# INA226-Current-Sensors.net
KiCad netlist of a schematic drawn in Altium Designer
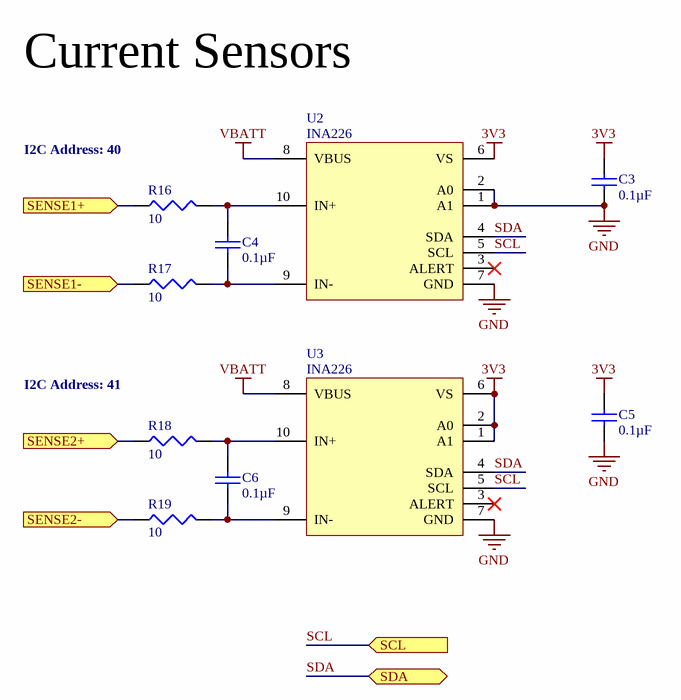
[diagram p0: INA226-Current-Sensors.SchDoc]

(export (version "E")
  (design (tool "Eeschema 10.0.6"))
  (components
    (comp (ref "C3")
      (value "0.1µF")
      (footprint "TDK-CGA2B")
      (description "CAP CER 0.1UF 50V X7R 0402")
      (fields
        (field (name "PART NUMBER") "PC-TDK-02262")
        (field (name "MANUFACTURER PART NUMBER") "CGA2B3X7R1H104M050BB")
        (field (name "PUBLISHER") "AlbertaSat")
      )
      (libsource (lib "Database") (part "Cap"))
    )
    (comp (ref "C4")
      (value "0.1µF")
      (footprint "TDK-CGA5L")
      (description "CAP CER 0.1UF 50V NP0 1206")
      (fields
        (field (name "PART NUMBER") "PC-TDK-02295")
        (field (name "MANUFACTURER PART NUMBER") "CGA5L2NP01H104J160AA")
        (field (name "PUBLISHER") "AlbertaSat")
      )
      (libsource (lib "Database") (part "Cap"))
    )
    (comp (ref "C5")
      (value "0.1µF")
      (footprint "TDK-CGA2B")
      (description "CAP CER 0.1UF 50V X7R 0402")
      (fields
        (field (name "PART NUMBER") "PC-TDK-02262")
        (field (name "MANUFACTURER PART NUMBER") "CGA2B3X7R1H104M050BB")
        (field (name "PUBLISHER") "AlbertaSat")
      )
      (libsource (lib "Database") (part "Cap"))
    )
    (comp (ref "C6")
      (value "0.1µF")
      (footprint "TDK-CGA5L")
      (description "CAP CER 0.1UF 50V NP0 1206")
      (fields
        (field (name "PART NUMBER") "PC-TDK-02295")
        (field (name "MANUFACTURER PART NUMBER") "CGA5L2NP01H104J160AA")
        (field (name "PUBLISHER") "AlbertaSat")
      )
      (libsource (lib "Database") (part "Cap"))
    )
    (comp (ref "R16")
      (value "10")
      (footprint "PANA-ERA2A")
      (description "RES SMD 10 OHM 0.5% 1/16W 0402")
      (fields
        (field (name "PART NUMBER") "13235")
        (field (name "MANUFACTURER PART NUMBER") "ERA-2AKD100X")
        (field (name "PUBLISHER") "Altium Limited")
      )
      (libsource (lib "Database") (part "Res3"))
    )
    (comp (ref "R17")
      (value "10")
      (footprint "PANA-ERA2A")
      (description "RES SMD 10 OHM 0.5% 1/16W 0402")
      (fields
        (field (name "PART NUMBER") "13235")
        (field (name "MANUFACTURER PART NUMBER") "ERA-2AKD100X")
        (field (name "PUBLISHER") "Altium Limited")
      )
      (libsource (lib "Database") (part "Res3"))
    )
    (comp (ref "R18")
      (value "10")
      (footprint "PANA-ERA2A")
      (description "RES SMD 10 OHM 0.5% 1/16W 0402")
      (fields
        (field (name "PART NUMBER") "13235")
        (field (name "MANUFACTURER PART NUMBER") "ERA-2AKD100X")
        (field (name "PUBLISHER") "Altium Limited")
      )
      (libsource (lib "Database") (part "Res3"))
    )
    (comp (ref "R19")
      (value "10")
      (footprint "PANA-ERA2A")
      (description "RES SMD 10 OHM 0.5% 1/16W 0402")
      (fields
        (field (name "PART NUMBER") "13235")
        (field (name "MANUFACTURER PART NUMBER") "ERA-2AKD100X")
        (field (name "PUBLISHER") "Altium Limited")
      )
      (libsource (lib "Database") (part "Res3"))
    )
    (comp (ref "U2")
      (value "INA226")
      (footprint "TI-DGS")
      (description "IC MONITOR PWR/CURR BIDIR 10MSOP")
      (fields (field (name "PART NUMBER") "19") (field (name "MANUFACTURER PART NUMBER") "INA226AQDGSRQ1"))
      (libsource (lib "Database") (part "INA226AQ"))
    )
    (comp (ref "U3")
      (value "INA226")
      (footprint "TI-DGS")
      (description "IC MONITOR PWR/CURR BIDIR 10MSOP")
      (fields (field (name "PART NUMBER") "19") (field (name "MANUFACTURER PART NUMBER") "INA226AQDGSRQ1"))
      (libsource (lib "Database") (part "INA226AQ"))
    )
  )
  (nets
    (net (code "2") (name "/SCL") (class "Default")
      (node (ref "U2") (pin "5") (pinfunction "SCL_5") (pintype "passive"))
      (node (ref "U3") (pin "5") (pinfunction "SCL_5") (pintype "passive"))
    )
    (net (code "3") (name "/SDA") (class "Default")
      (node (ref "U2") (pin "4") (pinfunction "SDA_4") (pintype "passive"))
      (node (ref "U3") (pin "4") (pinfunction "SDA_4") (pintype "passive"))
    )
    (net (code "4") (name "/SENSE1+") (class "Default")
      (node (ref "R16") (pin "1") (pinfunction "1_1") (pintype "passive"))
    )
    (net (code "5") (name "/SENSE1-") (class "Default")
      (node (ref "R17") (pin "1") (pinfunction "1_1") (pintype "passive"))
    )
    (net (code "6") (name "/SENSE2+") (class "Default")
      (node (ref "R18") (pin "1") (pinfunction "1_1") (pintype "passive"))
    )
    (net (code "7") (name "/SENSE2-") (class "Default")
      (node (ref "R19") (pin "1") (pinfunction "1_1") (pintype "passive"))
    )
    (net (code "8") (name "3V3") (class "Default")
      (node (ref "C3") (pin "2") (pinfunction "2_2") (pintype "passive"))
      (node (ref "C5") (pin "2") (pinfunction "2_2") (pintype "passive"))
      (node (ref "U2") (pin "6") (pinfunction "VS_6") (pintype "passive"))
      (node (ref "U3") (pin "1") (pinfunction "A1_1") (pintype "passive"))
      (node (ref "U3") (pin "2") (pinfunction "A0_2") (pintype "passive"))
      (node (ref "U3") (pin "6") (pinfunction "VS_6") (pintype "passive"))
    )
    (net (code "9") (name "GND") (class "Default")
      (node (ref "C3") (pin "1") (pinfunction "1_1") (pintype "passive"))
      (node (ref "C5") (pin "1") (pinfunction "1_1") (pintype "passive"))
      (node (ref "U2") (pin "1") (pinfunction "A1_1") (pintype "passive"))
      (node (ref "U2") (pin "2") (pinfunction "A0_2") (pintype "passive"))
      (node (ref "U2") (pin "7") (pinfunction "GND_7") (pintype "passive"))
      (node (ref "U3") (pin "7") (pinfunction "GND_7") (pintype "passive"))
    )
    (net (code "10") (name "Net-(U2-IN+)") (class "Default")
      (node (ref "C4") (pin "2") (pinfunction "2_2") (pintype "passive"))
      (node (ref "R16") (pin "2") (pinfunction "2_2") (pintype "passive"))
      (node (ref "U2") (pin "10") (pinfunction "IN+_10") (pintype "passive"))
    )
    (net (code "11") (name "Net-(U2-IN-)") (class "Default")
      (node (ref "C4") (pin "1") (pinfunction "1_1") (pintype "passive"))
      (node (ref "R17") (pin "2") (pinfunction "2_2") (pintype "passive"))
      (node (ref "U2") (pin "9") (pinfunction "IN-_9") (pintype "passive"))
    )
    (net (code "12") (name "Net-(U3-IN+)") (class "Default")
      (node (ref "C6") (pin "2") (pinfunction "2_2") (pintype "passive"))
      (node (ref "R18") (pin "2") (pinfunction "2_2") (pintype "passive"))
      (node (ref "U3") (pin "10") (pinfunction "IN+_10") (pintype "passive"))
    )
    (net (code "13") (name "Net-(U3-IN-)") (class "Default")
      (node (ref "C6") (pin "1") (pinfunction "1_1") (pintype "passive"))
      (node (ref "R19") (pin "2") (pinfunction "2_2") (pintype "passive"))
      (node (ref "U3") (pin "9") (pinfunction "IN-_9") (pintype "passive"))
    )
    (net (code "14") (name "VBATT") (class "Default")
      (node (ref "U2") (pin "8") (pinfunction "VBUS_8") (pintype "passive"))
      (node (ref "U3") (pin "8") (pinfunction "VBUS_8") (pintype "passive"))
    )
    (net (code "15") (name "unconnected-(U2-ALERT-Pad3)") (class "Default")
      (node (ref "U2") (pin "3") (pinfunction "ALERT_3") (pintype "passive+no_connect"))
    )
    (net (code "16") (name "unconnected-(U3-ALERT-Pad3)") (class "Default")
      (node (ref "U3") (pin "3") (pinfunction "ALERT_3") (pintype "passive+no_connect"))
    )
  )
)
